# schematic.net
KiCad netlist of a schematic drawn in EAGLE
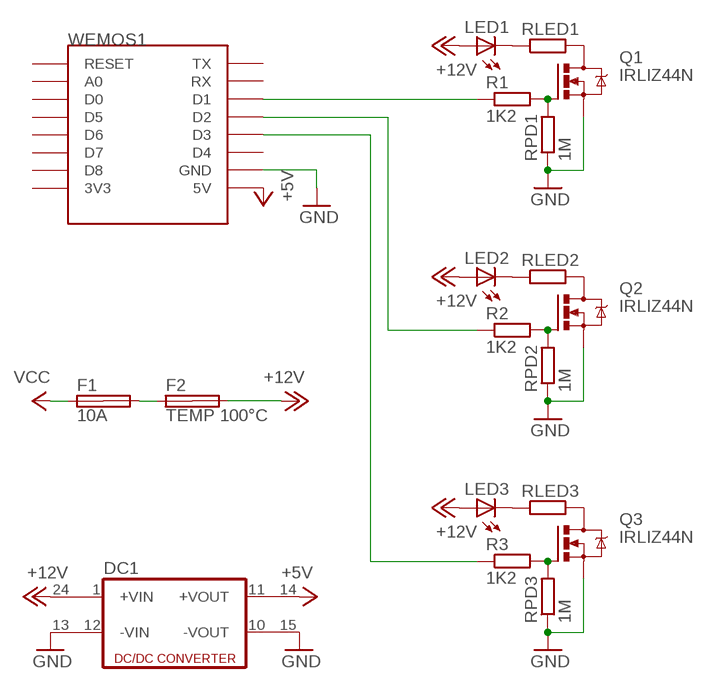
[diagram p0: schematic, sheet 1]

(export (version "E")
  (design (tool "Eeschema 10.0.6"))
  (components
    (comp (ref "DC1")
      (value "DC213R")
      (footprint "eagle-import:CMK")
      (libsource (lib "eagle-import") (part "DC213R"))
    )
    (comp (ref "F1")
      (value "10A")
      (footprint "eagle-import:SHK20L")
      (libsource (lib "eagle-import") (part "SHK20L"))
    )
    (comp (ref "F2")
      (value "TEMP 100°C")
      (footprint "eagle-import:SHK20L")
      (libsource (lib "eagle-import") (part "SHK20L"))
    )
    (comp (ref "LED1")
      (value "LED3MM")
      (footprint "eagle-import:LED3MM")
      (libsource (lib "eagle-import") (part "LED3MM"))
    )
    (comp (ref "LED2")
      (value "LED3MM")
      (footprint "eagle-import:LED3MM")
      (libsource (lib "eagle-import") (part "LED3MM"))
    )
    (comp (ref "LED3")
      (value "LED3MM")
      (footprint "eagle-import:LED3MM")
      (libsource (lib "eagle-import") (part "LED3MM"))
    )
    (comp (ref "Q1")
      (value "IRLIZ44N")
      (footprint "eagle-import:TO220BH")
      (libsource (lib "eagle-import") (part "IRLZ44Z"))
    )
    (comp (ref "Q2")
      (value "IRLIZ44N")
      (footprint "eagle-import:TO220BH")
      (libsource (lib "eagle-import") (part "IRLZ44Z"))
    )
    (comp (ref "Q3")
      (value "IRLIZ44N")
      (footprint "eagle-import:TO220BH")
      (libsource (lib "eagle-import") (part "IRLZ44Z"))
    )
    (comp (ref "R1")
      (value "1K2")
      (footprint "eagle-import:0204_5")
      (libsource (lib "eagle-import") (part "R-EU_0204/5"))
    )
    (comp (ref "R2")
      (value "1K2")
      (footprint "eagle-import:0204_5")
      (libsource (lib "eagle-import") (part "R-EU_0204/5"))
    )
    (comp (ref "R3")
      (value "1K2")
      (footprint "eagle-import:0204_5")
      (libsource (lib "eagle-import") (part "R-EU_0204/5"))
    )
    (comp (ref "RLED1")
      (value "R-EU_0204/5")
      (footprint "eagle-import:0204_5")
      (libsource (lib "eagle-import") (part "R-EU_0204/5"))
    )
    (comp (ref "RLED2")
      (value "R-EU_0204/5")
      (footprint "eagle-import:0204_5")
      (libsource (lib "eagle-import") (part "R-EU_0204/5"))
    )
    (comp (ref "RLED3")
      (value "R-EU_0204/5")
      (footprint "eagle-import:0204_5")
      (libsource (lib "eagle-import") (part "R-EU_0204/5"))
    )
    (comp (ref "RPD1")
      (value "1M")
      (footprint "eagle-import:0204_5")
      (libsource (lib "eagle-import") (part "R-EU_0204/5"))
    )
    (comp (ref "RPD2")
      (value "1M")
      (footprint "eagle-import:0204_5")
      (libsource (lib "eagle-import") (part "R-EU_0204/5"))
    )
    (comp (ref "RPD3")
      (value "1M")
      (footprint "eagle-import:0204_5")
      (libsource (lib "eagle-import") (part "R-EU_0204/5"))
    )
    (comp (ref "WEMOS1")
      (value "WEMOS-D1-MINI")
      (footprint "eagle-import:WEMOS-D1-MINI")
      (libsource (lib "eagle-import") (part "WEMOS-D1-MINI"))
    )
  )
  (nets
    (net (code "1") (name "+5V") (class "Default")
      (node (ref "DC1") (pin "14") (pinfunction "+VOUT1_14") (pintype "passive"))
      (node (ref "WEMOS1") (pin "5V") (pinfunction "5V_5V") (pintype "bidirectional"))
    )
    (net (code "2") (name "+12V") (class "Default")
      (node (ref "DC1") (pin "24") (pinfunction "+VIN1_24") (pintype "passive"))
      (node (ref "F2") (pin "2A") (pinfunction "2A_2A") (pintype "passive"))
      (node (ref "LED1") (pin "A") (pinfunction "A_A") (pintype "passive"))
      (node (ref "LED2") (pin "A") (pinfunction "A_A") (pintype "passive"))
      (node (ref "LED3") (pin "A") (pinfunction "A_A") (pintype "passive"))
    )
    (net (code "3") (name "GND") (class "Default")
      (node (ref "DC1") (pin "13") (pinfunction "-VIN1_13") (pintype "passive"))
      (node (ref "DC1") (pin "15") (pinfunction "-VOUT1_15") (pintype "passive"))
      (node (ref "Q1") (pin "S") (pinfunction "S_S") (pintype "passive"))
      (node (ref "Q2") (pin "S") (pinfunction "S_S") (pintype "passive"))
      (node (ref "Q3") (pin "S") (pinfunction "S_S") (pintype "passive"))
      (node (ref "RPD1") (pin "1") (pinfunction "1_1") (pintype "passive"))
      (node (ref "RPD2") (pin "1") (pinfunction "1_1") (pintype "passive"))
      (node (ref "RPD3") (pin "1") (pinfunction "1_1") (pintype "passive"))
      (node (ref "WEMOS1") (pin "GND") (pinfunction "GND_GND") (pintype "bidirectional"))
    )
    (net (code "4") (name "Net-(F1-Pad2A)") (class "Default")
      (node (ref "F1") (pin "2A") (pinfunction "2A_2A") (pintype "passive"))
      (node (ref "F2") (pin "1A") (pinfunction "1A_1A") (pintype "passive"))
    )
    (net (code "5") (name "Net-(LED1-C)") (class "Default")
      (node (ref "LED1") (pin "K") (pinfunction "C_K") (pintype "passive"))
      (node (ref "RLED1") (pin "1") (pinfunction "1_1") (pintype "passive"))
    )
    (net (code "6") (name "Net-(LED2-C)") (class "Default")
      (node (ref "LED2") (pin "K") (pinfunction "C_K") (pintype "passive"))
      (node (ref "RLED2") (pin "1") (pinfunction "1_1") (pintype "passive"))
    )
    (net (code "7") (name "Net-(LED3-C)") (class "Default")
      (node (ref "LED3") (pin "K") (pinfunction "C_K") (pintype "passive"))
      (node (ref "RLED3") (pin "1") (pinfunction "1_1") (pintype "passive"))
    )
    (net (code "8") (name "Net-(Q1-PadD)") (class "Default")
      (node (ref "Q1") (pin "D") (pinfunction "D_D") (pintype "passive"))
      (node (ref "RLED1") (pin "2") (pinfunction "2_2") (pintype "passive"))
    )
    (net (code "9") (name "Net-(Q1-PadG)") (class "Default")
      (node (ref "Q1") (pin "G") (pinfunction "G_G") (pintype "passive"))
      (node (ref "R1") (pin "2") (pinfunction "2_2") (pintype "passive"))
      (node (ref "RPD1") (pin "2") (pinfunction "2_2") (pintype "passive"))
    )
    (net (code "10") (name "Net-(Q2-PadD)") (class "Default")
      (node (ref "Q2") (pin "D") (pinfunction "D_D") (pintype "passive"))
      (node (ref "RLED2") (pin "2") (pinfunction "2_2") (pintype "passive"))
    )
    (net (code "11") (name "Net-(Q2-PadG)") (class "Default")
      (node (ref "Q2") (pin "G") (pinfunction "G_G") (pintype "passive"))
      (node (ref "R2") (pin "2") (pinfunction "2_2") (pintype "passive"))
      (node (ref "RPD2") (pin "2") (pinfunction "2_2") (pintype "passive"))
    )
    (net (code "12") (name "Net-(Q3-PadD)") (class "Default")
      (node (ref "Q3") (pin "D") (pinfunction "D_D") (pintype "passive"))
      (node (ref "RLED3") (pin "2") (pinfunction "2_2") (pintype "passive"))
    )
    (net (code "13") (name "Net-(Q3-PadG)") (class "Default")
      (node (ref "Q3") (pin "G") (pinfunction "G_G") (pintype "passive"))
      (node (ref "R3") (pin "2") (pinfunction "2_2") (pintype "passive"))
      (node (ref "RPD3") (pin "2") (pinfunction "2_2") (pintype "passive"))
    )
    (net (code "14") (name "Net-(R1-Pad1)") (class "Default")
      (node (ref "R1") (pin "1") (pinfunction "1_1") (pintype "passive"))
      (node (ref "WEMOS1") (pin "D1") (pinfunction "D1_D1") (pintype "bidirectional"))
    )
    (net (code "15") (name "Net-(R2-Pad1)") (class "Default")
      (node (ref "R2") (pin "1") (pinfunction "1_1") (pintype "passive"))
      (node (ref "WEMOS1") (pin "D2") (pinfunction "D2_D2") (pintype "bidirectional"))
    )
    (net (code "16") (name "Net-(R3-Pad1)") (class "Default")
      (node (ref "R3") (pin "1") (pinfunction "1_1") (pintype "passive"))
      (node (ref "WEMOS1") (pin "D3") (pinfunction "D3_D3") (pintype "bidirectional"))
    )
    (net (code "17") (name "VCC") (class "Default")
      (node (ref "F1") (pin "1A") (pinfunction "1A_1A") (pintype "passive"))
    )
    (net (code "18") (name "unconnected-(DC1-+VIN-Pad1)") (class "Default")
      (node (ref "DC1") (pin "1") (pinfunction "+VIN_1") (pintype "passive"))
    )
    (net (code "19") (name "unconnected-(DC1-+VOUT-Pad11)") (class "Default")
      (node (ref "DC1") (pin "11") (pinfunction "+VOUT_11") (pintype "passive"))
    )
    (net (code "20") (name "unconnected-(DC1--VIN-Pad12)") (class "Default")
      (node (ref "DC1") (pin "12") (pinfunction "-VIN_12") (pintype "passive"))
    )
    (net (code "21") (name "unconnected-(DC1--VOUT-Pad10)") (class "Default")
      (node (ref "DC1") (pin "10") (pinfunction "-VOUT_10") (pintype "passive"))
    )
    (net (code "22") (name "unconnected-(F1-Pad1B)") (class "Default")
      (node (ref "F1") (pin "1B") (pinfunction "1B_1B") (pintype "passive"))
    )
    (net (code "23") (name "unconnected-(F1-Pad2B)") (class "Default")
      (node (ref "F1") (pin "2B") (pinfunction "2B_2B") (pintype "passive"))
    )
    (net (code "24") (name "unconnected-(F2-Pad1B)") (class "Default")
      (node (ref "F2") (pin "1B") (pinfunction "1B_1B") (pintype "passive"))
    )
    (net (code "25") (name "unconnected-(F2-Pad2B)") (class "Default")
      (node (ref "F2") (pin "2B") (pinfunction "2B_2B") (pintype "passive"))
    )
    (net (code "26") (name "unconnected-(WEMOS1-Pad3V3)") (class "Default")
      (node (ref "WEMOS1") (pin "3V3") (pinfunction "3V3_3V3") (pintype "bidirectional"))
    )
    (net (code "27") (name "unconnected-(WEMOS1-PadA0)") (class "Default")
      (node (ref "WEMOS1") (pin "A0") (pinfunction "A0_A0") (pintype "bidirectional"))
    )
    (net (code "28") (name "unconnected-(WEMOS1-PadD0)") (class "Default")
      (node (ref "WEMOS1") (pin "D0") (pinfunction "D0_D0") (pintype "bidirectional"))
    )
    (net (code "29") (name "unconnected-(WEMOS1-PadD4)") (class "Default")
      (node (ref "WEMOS1") (pin "D4") (pinfunction "D4_D4") (pintype "bidirectional"))
    )
    (net (code "30") (name "unconnected-(WEMOS1-PadD5)") (class "Default")
      (node (ref "WEMOS1") (pin "D5") (pinfunction "D5_D5") (pintype "bidirectional"))
    )
    (net (code "31") (name "unconnected-(WEMOS1-PadD6)") (class "Default")
      (node (ref "WEMOS1") (pin "D6") (pinfunction "D6_D6") (pintype "bidirectional"))
    )
    (net (code "32") (name "unconnected-(WEMOS1-PadD7)") (class "Default")
      (node (ref "WEMOS1") (pin "D7") (pinfunction "D7_D7") (pintype "bidirectional"))
    )
    (net (code "33") (name "unconnected-(WEMOS1-PadD8)") (class "Default")
      (node (ref "WEMOS1") (pin "D8") (pinfunction "D8_D8") (pintype "bidirectional"))
    )
    (net (code "34") (name "unconnected-(WEMOS1-PadRESET)") (class "Default")
      (node (ref "WEMOS1") (pin "RESET") (pinfunction "RESET_RESET") (pintype "bidirectional"))
    )
    (net (code "35") (name "unconnected-(WEMOS1-PadRX)") (class "Default")
      (node (ref "WEMOS1") (pin "RX") (pinfunction "RX_RX") (pintype "bidirectional"))
    )
    (net (code "36") (name "unconnected-(WEMOS1-PadTX)") (class "Default")
      (node (ref "WEMOS1") (pin "TX") (pinfunction "TX_TX") (pintype "bidirectional"))
    )
  )
)
